# rpi-sensor-hat.net
KiCad netlist of a schematic drawn in EAGLE
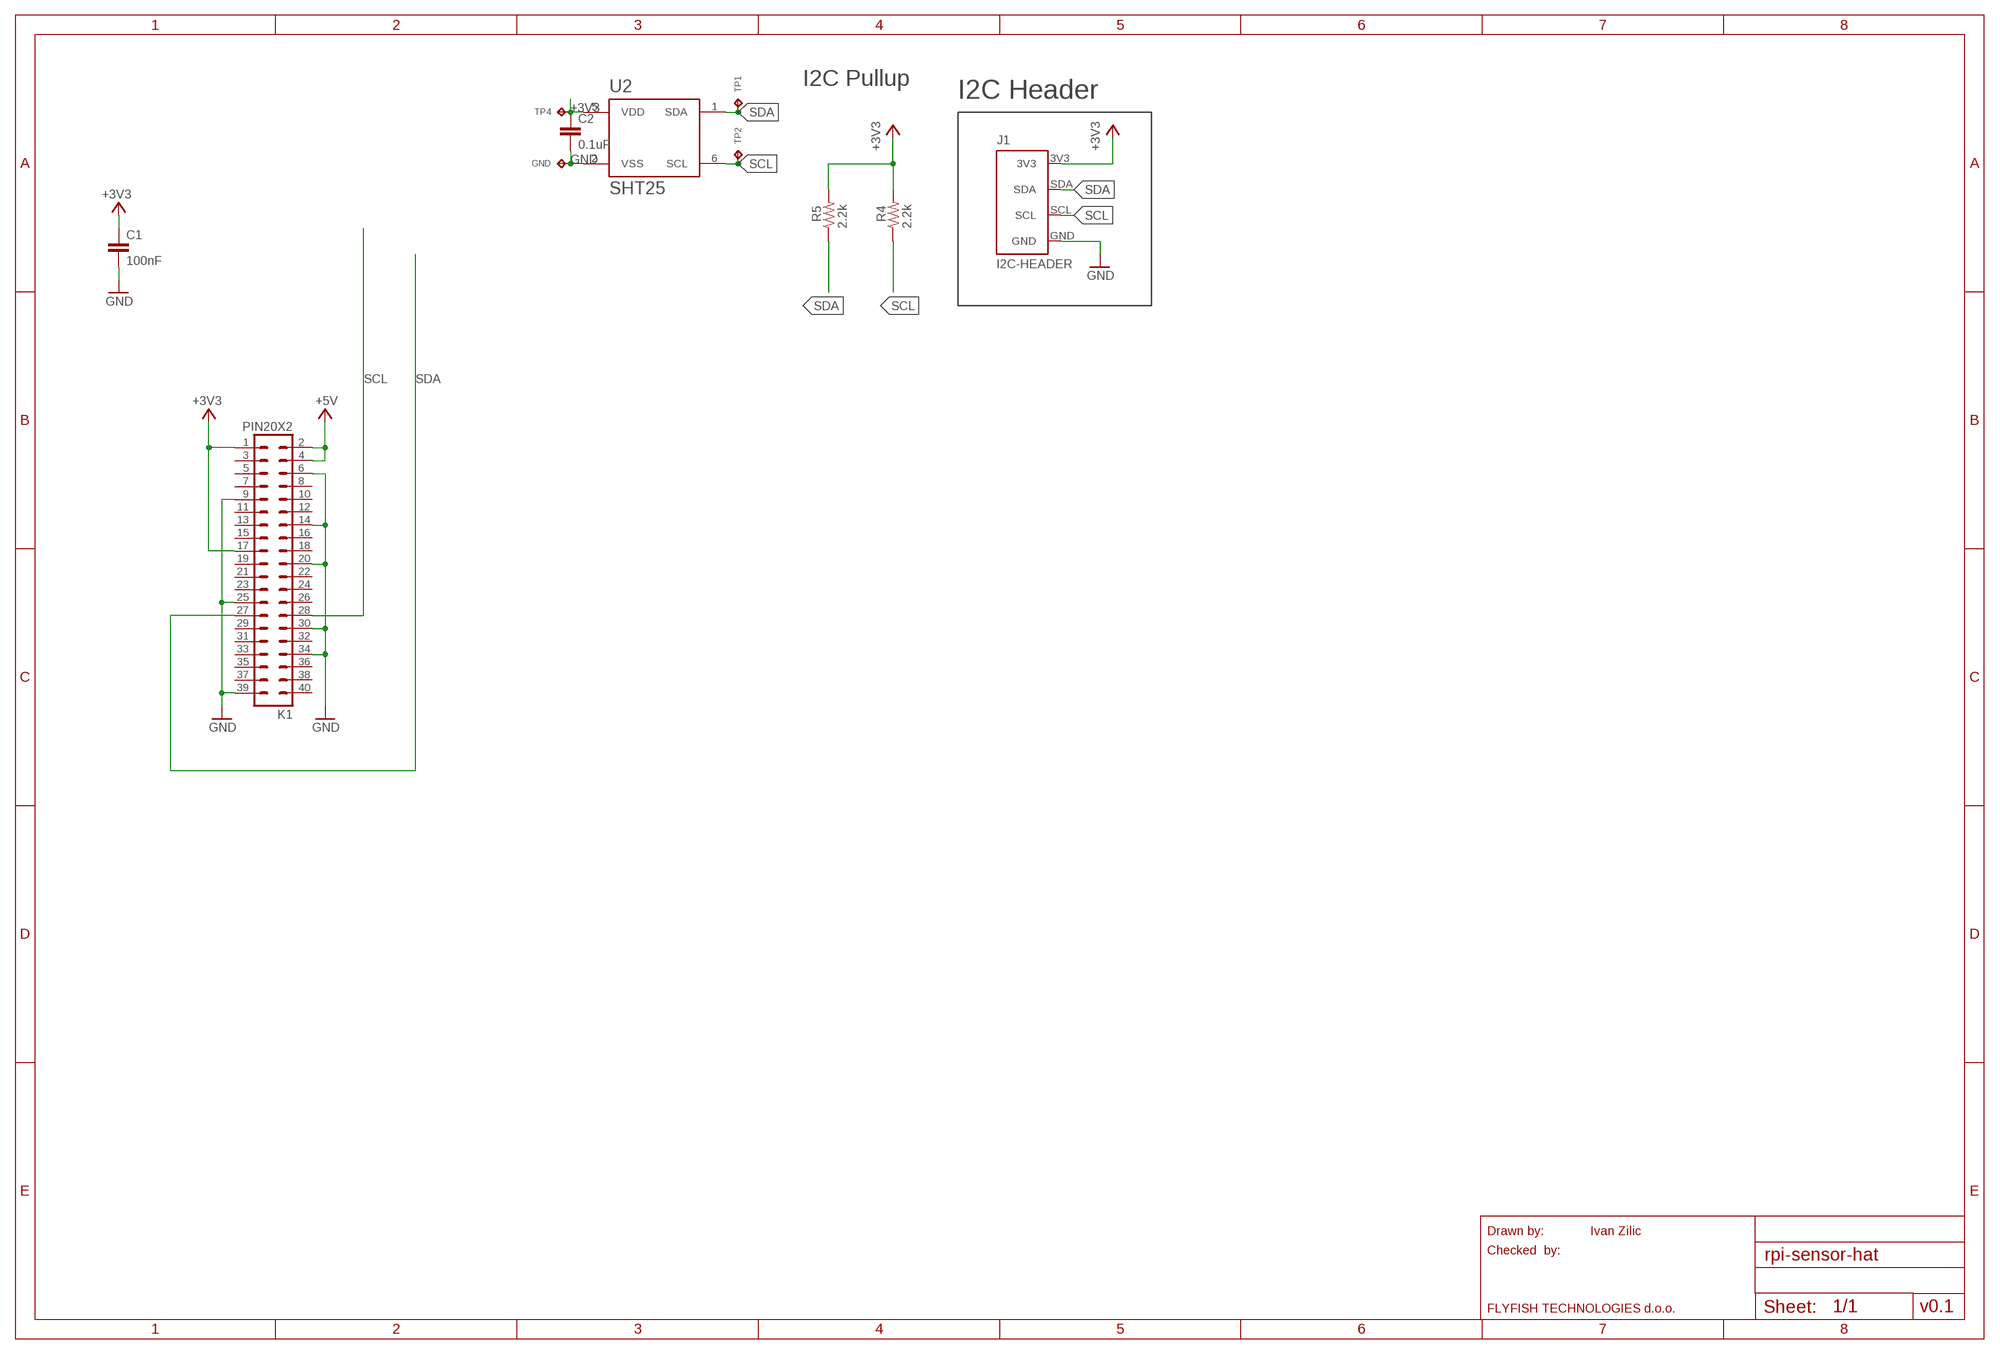
[diagram p0: schematic, sheet 1]

(export (version "E")
  (design (tool "Eeschema 10.0.6"))
  (components
    (comp (ref "C1")
      (value "100nF")
      (footprint "eagle-import:C0805K")
      (libsource (lib "eagle-import") (part "C-EUC0805K"))
    )
    (comp (ref "C2")
      (value "0.1uF")
      (footprint "eagle-import:C0603")
      (fields (field (name "MANUFACTURER") "Kemet") (field (name "MPN") "C0603C104K5RACTU"))
      (libsource (lib "eagle-import") (part "0.1UF-C0603C104K5RACTU"))
    )
    (comp (ref "GND")
      (value "TPTP06R")
      (footprint "eagle-import:TP06R")
      (libsource (lib "eagle-import") (part "TPTP06R"))
    )
    (comp (ref "J1")
      (value "I2C-HEADER")
      (footprint "eagle-import:HEADER-I2C")
      (libsource (lib "eagle-import") (part "HEADER-I2C"))
    )
    (comp (ref "K1")
      (value "PIN20X2")
      (footprint "eagle-import:PIN_20X2")
      (libsource (lib "eagle-import") (part "PIN20X2"))
    )
    (comp (ref "R4")
      (value "2.2k")
      (footprint "eagle-import:RC0603N")
      (fields (field (name "MANUFACTURER") "Yageo") (field (name "MPN") "RC0603JR-072K2L"))
      (libsource (lib "eagle-import") (part "2.2K-RC0603JR-072K2L"))
    )
    (comp (ref "R5")
      (value "2.2k")
      (footprint "eagle-import:RC0603N")
      (fields (field (name "MANUFACTURER") "Yageo") (field (name "MPN") "RC0603JR-072K2L"))
      (libsource (lib "eagle-import") (part "2.2K-RC0603JR-072K2L"))
    )
    (comp (ref "TP1")
      (value "TPTP06R")
      (footprint "eagle-import:TP06R")
      (libsource (lib "eagle-import") (part "TPTP06R"))
    )
    (comp (ref "TP2")
      (value "TPTP06R")
      (footprint "eagle-import:TP06R")
      (libsource (lib "eagle-import") (part "TPTP06R"))
    )
    (comp (ref "TP4")
      (value "TPTP06R")
      (footprint "eagle-import:TP06R")
      (libsource (lib "eagle-import") (part "TPTP06R"))
    )
    (comp (ref "U2")
      (value "SHT25")
      (footprint "eagle-import:SHT2X")
      (fields (field (name "MANUFACTURER") "Sensirion AG"))
      (libsource (lib "eagle-import") (part "SHT25"))
    )
  )
  (nets
    (net (code "1") (name "+3V3") (class "Default")
      (node (ref "C1") (pin "1") (pinfunction "1_1") (pintype "passive"))
      (node (ref "C2") (pin "1") (pinfunction "1_1") (pintype "passive"))
      (node (ref "J1") (pin "3V3") (pinfunction "3V3_3V3") (pintype "bidirectional"))
      (node (ref "K1") (pin "1") (pinfunction "1_1") (pintype "passive"))
      (node (ref "K1") (pin "17") (pinfunction "17_17") (pintype "passive"))
      (node (ref "R4") (pin "2") (pinfunction "2_2") (pintype "passive"))
      (node (ref "R5") (pin "2") (pinfunction "2_2") (pintype "passive"))
      (node (ref "TP4") (pin "TP") (pinfunction "TP_TP") (pintype "input"))
      (node (ref "U2") (pin "5") (pinfunction "VDD_5") (pintype "power_in"))
    )
    (net (code "2") (name "+5V") (class "Default")
      (node (ref "K1") (pin "2") (pinfunction "2_2") (pintype "passive"))
      (node (ref "K1") (pin "4") (pinfunction "4_4") (pintype "passive"))
    )
    (net (code "3") (name "GND") (class "Default")
      (node (ref "C1") (pin "2") (pinfunction "2_2") (pintype "passive"))
      (node (ref "C2") (pin "2") (pinfunction "2_2") (pintype "passive"))
      (node (ref "GND") (pin "TP") (pinfunction "TP_TP") (pintype "input"))
      (node (ref "J1") (pin "GND") (pinfunction "GND_GND") (pintype "bidirectional"))
      (node (ref "K1") (pin "14") (pinfunction "14_14") (pintype "passive"))
      (node (ref "K1") (pin "20") (pinfunction "20_20") (pintype "passive"))
      (node (ref "K1") (pin "25") (pinfunction "25_25") (pintype "passive"))
      (node (ref "K1") (pin "30") (pinfunction "30_30") (pintype "passive"))
      (node (ref "K1") (pin "34") (pinfunction "34_34") (pintype "passive"))
      (node (ref "K1") (pin "39") (pinfunction "39_39") (pintype "passive"))
      (node (ref "K1") (pin "6") (pinfunction "6_6") (pintype "passive"))
      (node (ref "K1") (pin "9") (pinfunction "9_9") (pintype "passive"))
      (node (ref "U2") (pin "2") (pinfunction "VSS_2") (pintype "power_in"))
    )
    (net (code "4") (name "SCL") (class "Default")
      (node (ref "J1") (pin "SCL") (pinfunction "SCL_SCL") (pintype "bidirectional"))
      (node (ref "K1") (pin "28") (pinfunction "28_28") (pintype "passive"))
      (node (ref "R4") (pin "1") (pinfunction "1_1") (pintype "passive"))
      (node (ref "TP2") (pin "TP") (pinfunction "TP_TP") (pintype "input"))
      (node (ref "U2") (pin "6") (pinfunction "SCL_6") (pintype "bidirectional"))
    )
    (net (code "5") (name "SDA") (class "Default")
      (node (ref "J1") (pin "SDA") (pinfunction "SDA_SDA") (pintype "bidirectional"))
      (node (ref "K1") (pin "27") (pinfunction "27_27") (pintype "passive"))
      (node (ref "R5") (pin "1") (pinfunction "1_1") (pintype "passive"))
      (node (ref "TP1") (pin "TP") (pinfunction "TP_TP") (pintype "input"))
      (node (ref "U2") (pin "1") (pinfunction "SDA_1") (pintype "bidirectional"))
    )
    (net (code "6") (name "unconnected-(K1-Pad3)") (class "Default")
      (node (ref "K1") (pin "3") (pinfunction "3_3") (pintype "passive"))
    )
    (net (code "7") (name "unconnected-(K1-Pad5)") (class "Default")
      (node (ref "K1") (pin "5") (pinfunction "5_5") (pintype "passive"))
    )
    (net (code "8") (name "unconnected-(K1-Pad7)") (class "Default")
      (node (ref "K1") (pin "7") (pinfunction "7_7") (pintype "passive"))
    )
    (net (code "9") (name "unconnected-(K1-Pad8)") (class "Default")
      (node (ref "K1") (pin "8") (pinfunction "8_8") (pintype "passive"))
    )
    (net (code "10") (name "unconnected-(K1-Pad10)") (class "Default")
      (node (ref "K1") (pin "10") (pinfunction "10_10") (pintype "passive"))
    )
    (net (code "11") (name "unconnected-(K1-Pad11)") (class "Default")
      (node (ref "K1") (pin "11") (pinfunction "11_11") (pintype "passive"))
    )
    (net (code "12") (name "unconnected-(K1-Pad12)") (class "Default")
      (node (ref "K1") (pin "12") (pinfunction "12_12") (pintype "passive"))
    )
    (net (code "13") (name "unconnected-(K1-Pad13)") (class "Default")
      (node (ref "K1") (pin "13") (pinfunction "13_13") (pintype "passive"))
    )
    (net (code "14") (name "unconnected-(K1-Pad15)") (class "Default")
      (node (ref "K1") (pin "15") (pinfunction "15_15") (pintype "passive"))
    )
    (net (code "15") (name "unconnected-(K1-Pad16)") (class "Default")
      (node (ref "K1") (pin "16") (pinfunction "16_16") (pintype "passive"))
    )
    (net (code "16") (name "unconnected-(K1-Pad18)") (class "Default")
      (node (ref "K1") (pin "18") (pinfunction "18_18") (pintype "passive"))
    )
    (net (code "17") (name "unconnected-(K1-Pad19)") (class "Default")
      (node (ref "K1") (pin "19") (pinfunction "19_19") (pintype "passive"))
    )
    (net (code "18") (name "unconnected-(K1-Pad21)") (class "Default")
      (node (ref "K1") (pin "21") (pinfunction "21_21") (pintype "passive"))
    )
    (net (code "19") (name "unconnected-(K1-Pad22)") (class "Default")
      (node (ref "K1") (pin "22") (pinfunction "22_22") (pintype "passive"))
    )
    (net (code "20") (name "unconnected-(K1-Pad23)") (class "Default")
      (node (ref "K1") (pin "23") (pinfunction "23_23") (pintype "passive"))
    )
    (net (code "21") (name "unconnected-(K1-Pad24)") (class "Default")
      (node (ref "K1") (pin "24") (pinfunction "24_24") (pintype "passive"))
    )
    (net (code "22") (name "unconnected-(K1-Pad26)") (class "Default")
      (node (ref "K1") (pin "26") (pinfunction "26_26") (pintype "passive"))
    )
    (net (code "23") (name "unconnected-(K1-Pad29)") (class "Default")
      (node (ref "K1") (pin "29") (pinfunction "29_29") (pintype "passive"))
    )
    (net (code "24") (name "unconnected-(K1-Pad31)") (class "Default")
      (node (ref "K1") (pin "31") (pinfunction "31_31") (pintype "passive"))
    )
    (net (code "25") (name "unconnected-(K1-Pad32)") (class "Default")
      (node (ref "K1") (pin "32") (pinfunction "32_32") (pintype "passive"))
    )
    (net (code "26") (name "unconnected-(K1-Pad33)") (class "Default")
      (node (ref "K1") (pin "33") (pinfunction "33_33") (pintype "passive"))
    )
    (net (code "27") (name "unconnected-(K1-Pad35)") (class "Default")
      (node (ref "K1") (pin "35") (pinfunction "35_35") (pintype "passive"))
    )
    (net (code "28") (name "unconnected-(K1-Pad36)") (class "Default")
      (node (ref "K1") (pin "36") (pinfunction "36_36") (pintype "passive"))
    )
    (net (code "29") (name "unconnected-(K1-Pad37)") (class "Default")
      (node (ref "K1") (pin "37") (pinfunction "37_37") (pintype "passive"))
    )
    (net (code "30") (name "unconnected-(K1-Pad38)") (class "Default")
      (node (ref "K1") (pin "38") (pinfunction "38_38") (pintype "passive"))
    )
    (net (code "31") (name "unconnected-(K1-Pad40)") (class "Default")
      (node (ref "K1") (pin "40") (pinfunction "40_40") (pintype "passive"))
    )
  )
)
